# plan2.net
KiCad netlist of a schematic drawn in EAGLE
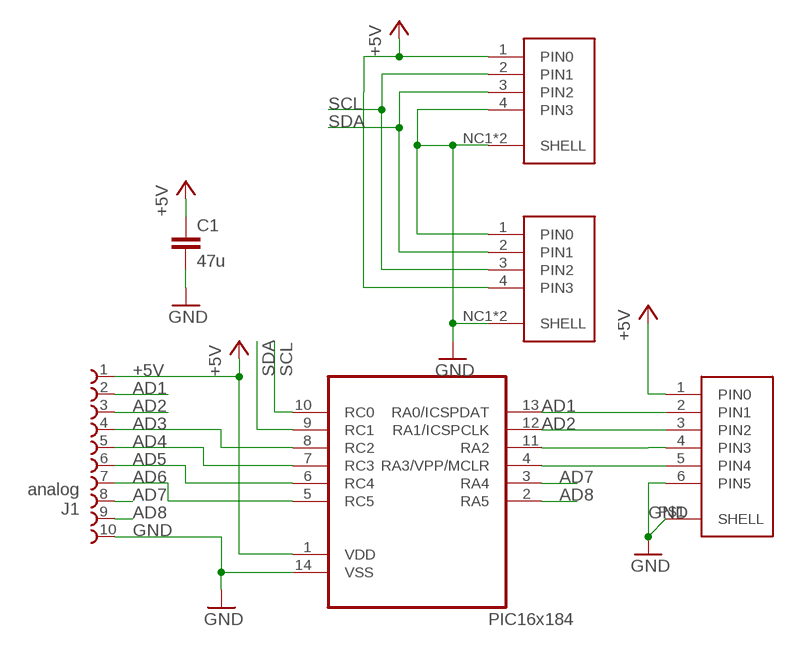
[diagram p0: schematic, sheet 1]

(export (version "E")
  (design (tool "Eeschema 10.0.6"))
  (components
    (comp (ref "C1")
      (value "47u")
      (footprint "eagle-import:C0805")
      (libsource (lib "eagle-import") (part "C-EUC0805"))
    )
    (comp (ref "J1")
      (value "analog")
      (footprint "eagle-import:68611014422")
      (libsource (lib "eagle-import") (part "68611014422"))
    )
    (comp (ref "MAINCON")
      (value "PIC16F18424")
      (footprint "eagle-import:14-TSSOP")
      (libsource (lib "eagle-import") (part "PIC16F18424"))
    )
    (comp (ref "U$2")
      (value "IIC1")
      (footprint "eagle-import:JST_ZH_4PIN")
      (libsource (lib "eagle-import") (part "JST_ZH_4PIN"))
    )
    (comp (ref "U$3")
      (value "IIC2")
      (footprint "eagle-import:JST_ZH_4PIN")
      (libsource (lib "eagle-import") (part "JST_ZH_4PIN"))
    )
    (comp (ref "U$4")
      (value "programming")
      (footprint "eagle-import:JST_ZH_6PIN")
      (libsource (lib "eagle-import") (part "JST_ZH_6PIN"))
    )
  )
  (nets
    (net (code "1") (name "+5V") (class "Default")
      (node (ref "C1") (pin "1") (pinfunction "1_1") (pintype "passive"))
      (node (ref "J1") (pin "1") (pinfunction "10_1") (pintype "passive"))
      (node (ref "MAINCON") (pin "1") (pinfunction "VDD_1") (pintype "bidirectional"))
      (node (ref "U$2") (pin "1") (pinfunction "PIN0_1") (pintype "bidirectional"))
      (node (ref "U$3") (pin "4") (pinfunction "PIN3_4") (pintype "bidirectional"))
      (node (ref "U$4") (pin "1") (pinfunction "PIN0_1") (pintype "bidirectional"))
    )
    (net (code "2") (name "/AD1") (class "Default")
      (node (ref "J1") (pin "2") (pinfunction "9_2") (pintype "passive"))
      (node (ref "MAINCON") (pin "13") (pinfunction "RA0/ICSPDAT_13") (pintype "bidirectional"))
      (node (ref "U$4") (pin "2") (pinfunction "PIN1_2") (pintype "bidirectional"))
    )
    (net (code "3") (name "/AD2") (class "Default")
      (node (ref "J1") (pin "3") (pinfunction "8_3") (pintype "passive"))
      (node (ref "MAINCON") (pin "12") (pinfunction "RA1/ICSPCLK_12") (pintype "bidirectional"))
      (node (ref "U$4") (pin "3") (pinfunction "PIN2_3") (pintype "bidirectional"))
    )
    (net (code "4") (name "/AD3") (class "Default")
      (node (ref "J1") (pin "4") (pinfunction "7_4") (pintype "passive"))
      (node (ref "MAINCON") (pin "8") (pinfunction "RC2_8") (pintype "bidirectional"))
    )
    (net (code "5") (name "/AD4") (class "Default")
      (node (ref "J1") (pin "5") (pinfunction "6_5") (pintype "passive"))
      (node (ref "MAINCON") (pin "7") (pinfunction "RC3_7") (pintype "bidirectional"))
    )
    (net (code "6") (name "/AD5") (class "Default")
      (node (ref "J1") (pin "6") (pinfunction "5_6") (pintype "passive"))
      (node (ref "MAINCON") (pin "6") (pinfunction "RC4_6") (pintype "bidirectional"))
    )
    (net (code "7") (name "/AD6") (class "Default")
      (node (ref "J1") (pin "7") (pinfunction "4_7") (pintype "passive"))
      (node (ref "MAINCON") (pin "5") (pinfunction "RC5_5") (pintype "bidirectional"))
    )
    (net (code "8") (name "/AD7") (class "Default")
      (node (ref "J1") (pin "8") (pinfunction "3_8") (pintype "passive"))
      (node (ref "MAINCON") (pin "3") (pinfunction "RA4_3") (pintype "bidirectional"))
    )
    (net (code "9") (name "/AD8") (class "Default")
      (node (ref "J1") (pin "9") (pinfunction "2_9") (pintype "passive"))
      (node (ref "MAINCON") (pin "2") (pinfunction "RA5_2") (pintype "bidirectional"))
    )
    (net (code "10") (name "/SCL") (class "Default")
      (node (ref "MAINCON") (pin "10") (pinfunction "RC0_10") (pintype "bidirectional"))
      (node (ref "U$2") (pin "2") (pinfunction "PIN1_2") (pintype "bidirectional"))
      (node (ref "U$3") (pin "3") (pinfunction "PIN2_3") (pintype "bidirectional"))
    )
    (net (code "11") (name "/SDA") (class "Default")
      (node (ref "MAINCON") (pin "9") (pinfunction "RC1_9") (pintype "bidirectional"))
      (node (ref "U$2") (pin "3") (pinfunction "PIN2_3") (pintype "bidirectional"))
      (node (ref "U$3") (pin "2") (pinfunction "PIN1_2") (pintype "bidirectional"))
    )
    (net (code "12") (name "GND") (class "Default")
      (node (ref "C1") (pin "2") (pinfunction "2_2") (pintype "passive"))
      (node (ref "J1") (pin "10") (pinfunction "1_10") (pintype "passive"))
      (node (ref "MAINCON") (pin "14") (pinfunction "VSS_14") (pintype "bidirectional"))
      (node (ref "U$2") (pin "4") (pinfunction "PIN3_4") (pintype "bidirectional"))
      (node (ref "U$2") (pin "NC1") (pinfunction "SHELL_NC1") (pintype "bidirectional"))
      (node (ref "U$2") (pin "NC2") (pinfunction "SHELL_NC2") (pintype "bidirectional"))
      (node (ref "U$3") (pin "1") (pinfunction "PIN0_1") (pintype "bidirectional"))
      (node (ref "U$3") (pin "NC1") (pinfunction "SHELL_NC1") (pintype "bidirectional"))
      (node (ref "U$3") (pin "NC2") (pinfunction "SHELL_NC2") (pintype "bidirectional"))
      (node (ref "U$4") (pin "6") (pinfunction "PIN5_6") (pintype "bidirectional"))
      (node (ref "U$4") (pin "P$1") (pinfunction "SHELL_P$1") (pintype "bidirectional"))
    )
    (net (code "13") (name "Net-(MAINCON-RA2)") (class "Default")
      (node (ref "MAINCON") (pin "11") (pinfunction "RA2_11") (pintype "bidirectional"))
      (node (ref "U$4") (pin "4") (pinfunction "PIN3_4") (pintype "bidirectional"))
    )
    (net (code "14") (name "Net-(MAINCON-RA3{slash}VPP{slash}MCLR)") (class "Default")
      (node (ref "MAINCON") (pin "4") (pinfunction "RA3/VPP/MCLR_4") (pintype "bidirectional"))
      (node (ref "U$4") (pin "5") (pinfunction "PIN4_5") (pintype "bidirectional"))
    )
  )
)
